# Breakout.net
KiCad netlist of a schematic drawn in EAGLE
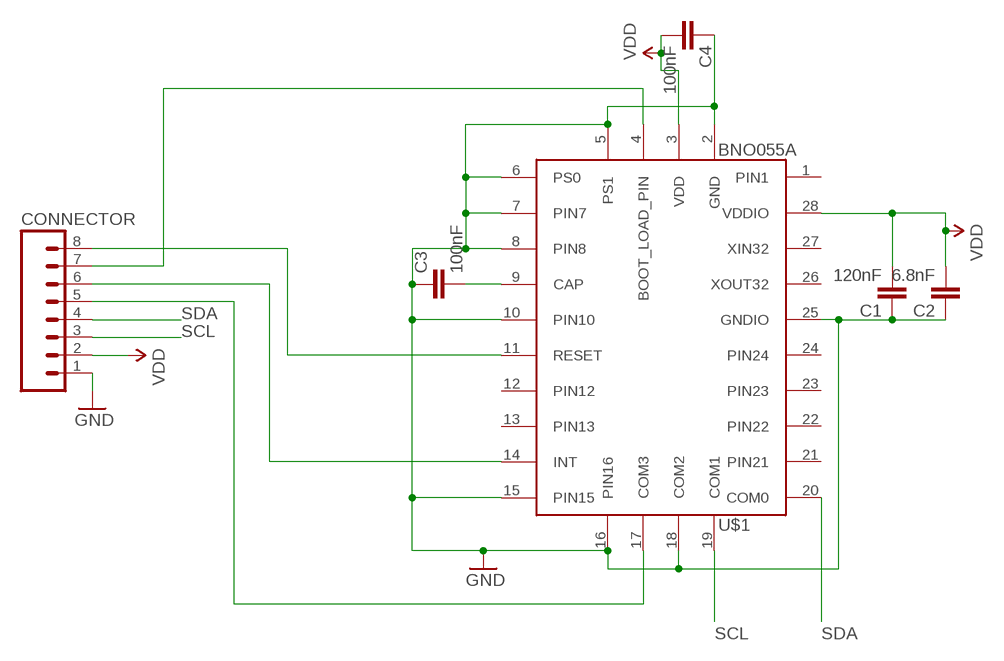
[diagram p0: schematic, sheet 1]

(export (version "E")
  (design (tool "Eeschema 10.0.6"))
  (components
    (comp (ref "C1")
      (value "120nF")
      (footprint "eagle-import:1206")
      (libsource (lib "eagle-import") (part "CAP1206"))
    )
    (comp (ref "C2")
      (value "6.8nF")
      (footprint "eagle-import:1206")
      (libsource (lib "eagle-import") (part "CAP1206"))
    )
    (comp (ref "C3")
      (value "100nF")
      (footprint "eagle-import:1206")
      (libsource (lib "eagle-import") (part "CAP1206"))
    )
    (comp (ref "C4")
      (value "100nF")
      (footprint "eagle-import:1206")
      (libsource (lib "eagle-import") (part "CAP1206"))
    )
    (comp (ref "CONNECTOR")
      (value "M08NO_SILK")
      (footprint "eagle-import:1X08_NO_SILK")
      (libsource (lib "eagle-import") (part "M08NO_SILK"))
    )
    (comp (ref "U$1")
      (value "BNO055A")
      (footprint "eagle-import:BNO055")
      (libsource (lib "eagle-import") (part "BNO055A"))
    )
  )
  (nets
    (net (code "1") (name "/SCL") (class "Default")
      (node (ref "CONNECTOR") (pin "3") (pinfunction "3_3") (pintype "passive"))
      (node (ref "U$1") (pin "19") (pinfunction "COM1_19") (pintype "bidirectional"))
    )
    (net (code "2") (name "/SDA") (class "Default")
      (node (ref "CONNECTOR") (pin "4") (pinfunction "4_4") (pintype "passive"))
      (node (ref "U$1") (pin "20") (pinfunction "COM0_20") (pintype "bidirectional"))
    )
    (net (code "3") (name "GND") (class "Default")
      (node (ref "C1") (pin "1") (pinfunction "1_1") (pintype "passive"))
      (node (ref "C2") (pin "1") (pinfunction "1_1") (pintype "passive"))
      (node (ref "C3") (pin "1") (pinfunction "1_1") (pintype "passive"))
      (node (ref "C4") (pin "1") (pinfunction "1_1") (pintype "passive"))
      (node (ref "CONNECTOR") (pin "1") (pinfunction "1_1") (pintype "passive"))
      (node (ref "U$1") (pin "10") (pinfunction "PIN10_10") (pintype "bidirectional"))
      (node (ref "U$1") (pin "15") (pinfunction "PIN15_15") (pintype "bidirectional"))
      (node (ref "U$1") (pin "16") (pinfunction "PIN16_16") (pintype "bidirectional"))
      (node (ref "U$1") (pin "18") (pinfunction "COM2_18") (pintype "bidirectional"))
      (node (ref "U$1") (pin "2") (pinfunction "GND_2") (pintype "bidirectional"))
      (node (ref "U$1") (pin "25") (pinfunction "GNDIO_25") (pintype "bidirectional"))
      (node (ref "U$1") (pin "5") (pinfunction "PS1_5") (pintype "bidirectional"))
      (node (ref "U$1") (pin "6") (pinfunction "PS0_6") (pintype "bidirectional"))
      (node (ref "U$1") (pin "7") (pinfunction "PIN7_7") (pintype "bidirectional"))
      (node (ref "U$1") (pin "8") (pinfunction "PIN8_8") (pintype "bidirectional"))
    )
    (net (code "4") (name "Net-(U$1-BOOT_LOAD_PIN)") (class "Default")
      (node (ref "CONNECTOR") (pin "7") (pinfunction "7_7") (pintype "passive"))
      (node (ref "U$1") (pin "4") (pinfunction "BOOT_LOAD_PIN_4") (pintype "bidirectional"))
    )
    (net (code "5") (name "Net-(U$1-CAP)") (class "Default")
      (node (ref "C3") (pin "2") (pinfunction "2_2") (pintype "passive"))
      (node (ref "U$1") (pin "9") (pinfunction "CAP_9") (pintype "bidirectional"))
    )
    (net (code "6") (name "Net-(U$1-COM3)") (class "Default")
      (node (ref "CONNECTOR") (pin "5") (pinfunction "5_5") (pintype "passive"))
      (node (ref "U$1") (pin "17") (pinfunction "COM3_17") (pintype "bidirectional"))
    )
    (net (code "7") (name "Net-(U$1-INT)") (class "Default")
      (node (ref "CONNECTOR") (pin "6") (pinfunction "6_6") (pintype "passive"))
      (node (ref "U$1") (pin "14") (pinfunction "INT_14") (pintype "bidirectional"))
    )
    (net (code "8") (name "Net-(U$1-RESET)") (class "Default")
      (node (ref "CONNECTOR") (pin "8") (pinfunction "8_8") (pintype "passive"))
      (node (ref "U$1") (pin "11") (pinfunction "RESET_11") (pintype "bidirectional"))
    )
    (net (code "9") (name "VDD") (class "Default")
      (node (ref "C1") (pin "2") (pinfunction "2_2") (pintype "passive"))
      (node (ref "C2") (pin "2") (pinfunction "2_2") (pintype "passive"))
      (node (ref "C4") (pin "2") (pinfunction "2_2") (pintype "passive"))
      (node (ref "CONNECTOR") (pin "2") (pinfunction "2_2") (pintype "passive"))
      (node (ref "U$1") (pin "28") (pinfunction "VDDIO_28") (pintype "bidirectional"))
      (node (ref "U$1") (pin "3") (pinfunction "VDD_3") (pintype "bidirectional"))
    )
    (net (code "10") (name "unconnected-(U$1-PIN1-Pad1)") (class "Default")
      (node (ref "U$1") (pin "1") (pinfunction "PIN1_1") (pintype "bidirectional"))
    )
    (net (code "11") (name "unconnected-(U$1-PIN12-Pad12)") (class "Default")
      (node (ref "U$1") (pin "12") (pinfunction "PIN12_12") (pintype "bidirectional"))
    )
    (net (code "12") (name "unconnected-(U$1-PIN13-Pad13)") (class "Default")
      (node (ref "U$1") (pin "13") (pinfunction "PIN13_13") (pintype "bidirectional"))
    )
    (net (code "13") (name "unconnected-(U$1-PIN21-Pad21)") (class "Default")
      (node (ref "U$1") (pin "21") (pinfunction "PIN21_21") (pintype "bidirectional"))
    )
    (net (code "14") (name "unconnected-(U$1-PIN22-Pad22)") (class "Default")
      (node (ref "U$1") (pin "22") (pinfunction "PIN22_22") (pintype "bidirectional"))
    )
    (net (code "15") (name "unconnected-(U$1-PIN23-Pad23)") (class "Default")
      (node (ref "U$1") (pin "23") (pinfunction "PIN23_23") (pintype "bidirectional"))
    )
    (net (code "16") (name "unconnected-(U$1-PIN24-Pad24)") (class "Default")
      (node (ref "U$1") (pin "24") (pinfunction "PIN24_24") (pintype "bidirectional"))
    )
    (net (code "17") (name "unconnected-(U$1-XIN32-Pad27)") (class "Default")
      (node (ref "U$1") (pin "27") (pinfunction "XIN32_27") (pintype "bidirectional"))
    )
    (net (code "18") (name "unconnected-(U$1-XOUT32-Pad26)") (class "Default")
      (node (ref "U$1") (pin "26") (pinfunction "XOUT32_26") (pintype "bidirectional"))
    )
  )
)
